# DRA818V_breakout_board.net
KiCad netlist of a schematic drawn in EAGLE
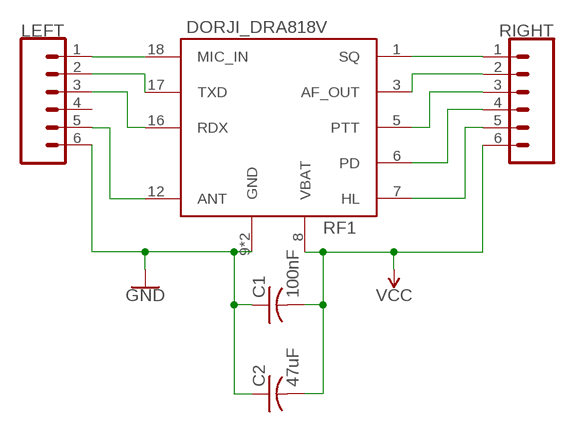
[diagram p0: schematic, sheet 1]

(export (version "E")
  (design (tool "Eeschema 10.0.6"))
  (components
    (comp (ref "C1")
      (value "100nF")
      (footprint "eagle-import:C0603")
      (libsource (lib "eagle-import") (part "C-USC0603"))
    )
    (comp (ref "C2")
      (value "47uF")
      (footprint "eagle-import:C0603")
      (libsource (lib "eagle-import") (part "C-USC0603"))
    )
    (comp (ref "LEFT")
      (value "CONN_06NO_SILK_FEMALE_PTH")
      (footprint "eagle-import:1X06_NO_SILK")
      (libsource (lib "eagle-import") (part "CONN_06NO_SILK_FEMALE_PTH"))
    )
    (comp (ref "RF1")
      (value "DORJI_DRA818V")
      (footprint "eagle-import:DORJI_DRA818V")
      (libsource (lib "eagle-import") (part "DORJI_DRA818V"))
    )
    (comp (ref "RIGHT")
      (value "CONN_06NO_SILK_FEMALE_PTH")
      (footprint "eagle-import:1X06_NO_SILK")
      (libsource (lib "eagle-import") (part "CONN_06NO_SILK_FEMALE_PTH"))
    )
  )
  (nets
    (net (code "1") (name "GND") (class "Default")
      (node (ref "C1") (pin "1") (pinfunction "1_1") (pintype "passive"))
      (node (ref "C2") (pin "1") (pinfunction "1_1") (pintype "passive"))
      (node (ref "LEFT") (pin "6") (pinfunction "6_6") (pintype "passive"))
      (node (ref "RF1") (pin "10") (pinfunction "GND_10") (pintype "power_in"))
      (node (ref "RF1") (pin "9") (pinfunction "GND_9") (pintype "power_in"))
    )
    (net (code "2") (name "Net-(RF1-AF_OUT)") (class "Default")
      (node (ref "RF1") (pin "3") (pinfunction "AF_OUT_3") (pintype "output"))
      (node (ref "RIGHT") (pin "2") (pinfunction "2_2") (pintype "passive"))
    )
    (net (code "3") (name "Net-(RF1-ANT)") (class "Default")
      (node (ref "LEFT") (pin "5") (pinfunction "5_5") (pintype "passive"))
      (node (ref "RF1") (pin "12") (pinfunction "ANT_12") (pintype "bidirectional"))
    )
    (net (code "4") (name "Net-(RF1-HL)") (class "Default")
      (node (ref "RF1") (pin "7") (pinfunction "HL_7") (pintype "input"))
      (node (ref "RIGHT") (pin "5") (pinfunction "5_5") (pintype "passive"))
    )
    (net (code "5") (name "Net-(RF1-MIC_IN)") (class "Default")
      (node (ref "LEFT") (pin "1") (pinfunction "1_1") (pintype "passive"))
      (node (ref "RF1") (pin "18") (pinfunction "MIC_IN_18") (pintype "input"))
    )
    (net (code "6") (name "Net-(RF1-PD)") (class "Default")
      (node (ref "RF1") (pin "6") (pinfunction "PD_6") (pintype "input"))
      (node (ref "RIGHT") (pin "4") (pinfunction "4_4") (pintype "passive"))
    )
    (net (code "7") (name "Net-(RF1-PTT)") (class "Default")
      (node (ref "RF1") (pin "5") (pinfunction "PTT_5") (pintype "input"))
      (node (ref "RIGHT") (pin "3") (pinfunction "3_3") (pintype "passive"))
    )
    (net (code "8") (name "Net-(RF1-RDX)") (class "Default")
      (node (ref "LEFT") (pin "3") (pinfunction "3_3") (pintype "passive"))
      (node (ref "RF1") (pin "16") (pinfunction "RDX_16") (pintype "input"))
    )
    (net (code "9") (name "Net-(RF1-SQ)") (class "Default")
      (node (ref "RF1") (pin "1") (pinfunction "SQ_1") (pintype "input"))
      (node (ref "RIGHT") (pin "1") (pinfunction "1_1") (pintype "passive"))
    )
    (net (code "10") (name "Net-(RF1-TXD)") (class "Default")
      (node (ref "LEFT") (pin "2") (pinfunction "2_2") (pintype "passive"))
      (node (ref "RF1") (pin "17") (pinfunction "TXD_17") (pintype "input"))
    )
    (net (code "11") (name "VCC") (class "Default")
      (node (ref "C1") (pin "2") (pinfunction "2_2") (pintype "passive"))
      (node (ref "C2") (pin "2") (pinfunction "2_2") (pintype "passive"))
      (node (ref "RF1") (pin "8") (pinfunction "VBAT_8") (pintype "power_in"))
      (node (ref "RIGHT") (pin "6") (pinfunction "6_6") (pintype "passive"))
    )
    (net (code "12") (name "unconnected-(LEFT-Pad4)") (class "Default")
      (node (ref "LEFT") (pin "4") (pinfunction "4_4") (pintype "passive"))
    )
  )
)
